# MM_Motor_Driver.net
KiCad netlist of a schematic drawn in Altium Designer
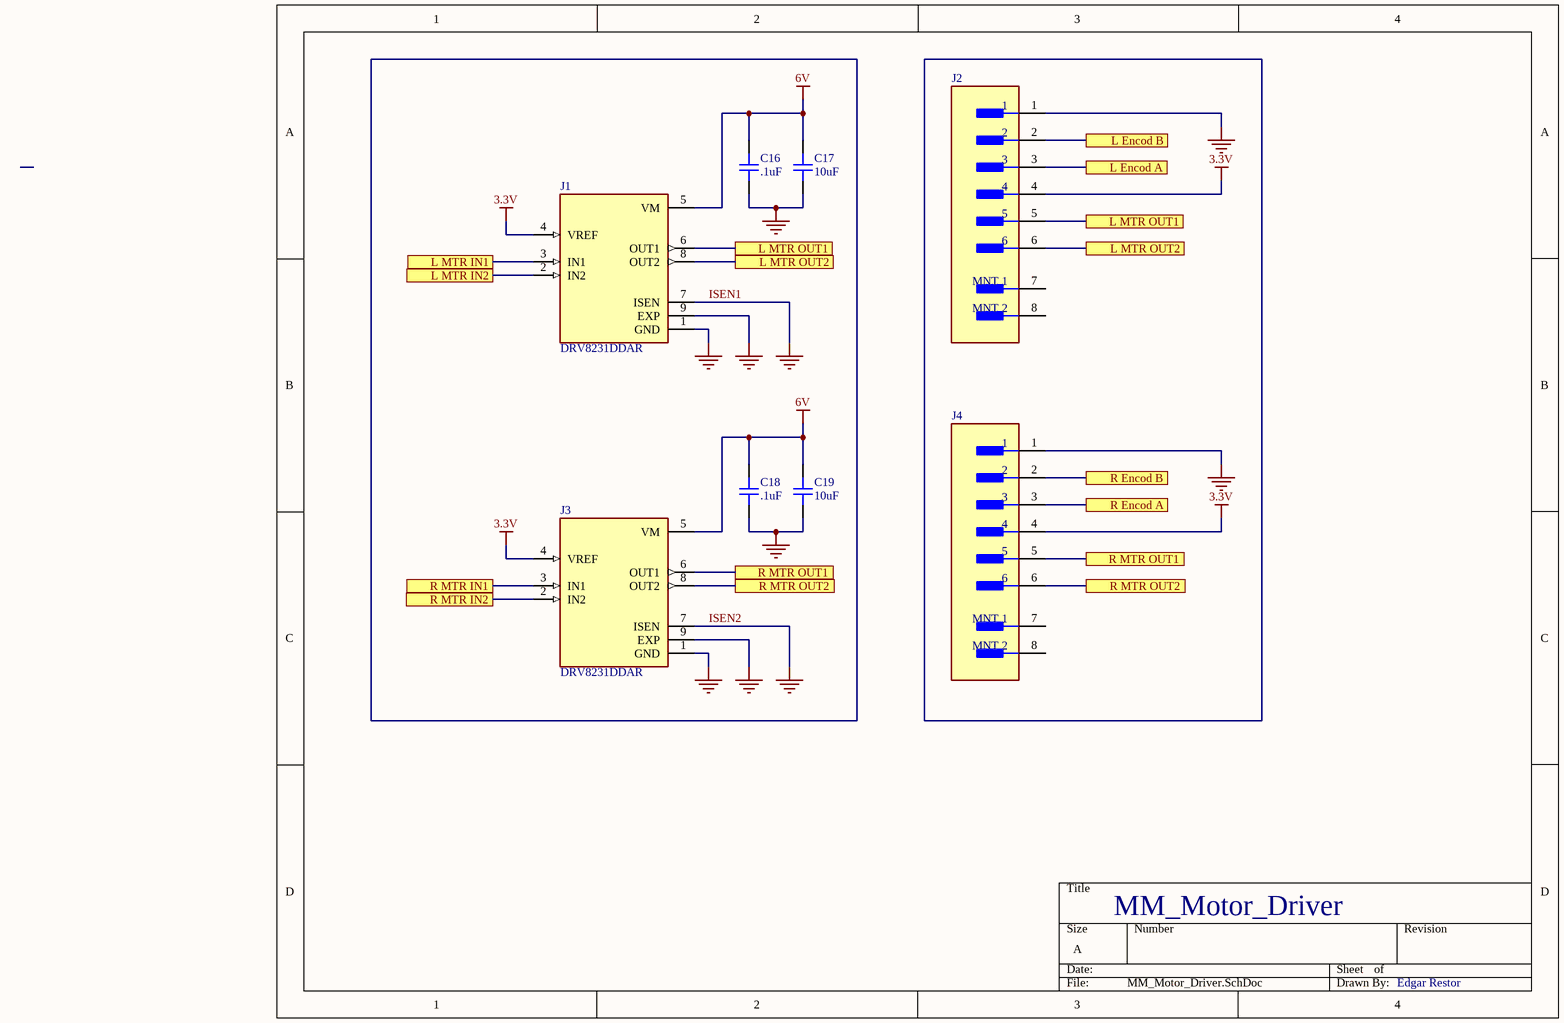
[diagram p0: MM_Motor_Driver.SchDoc]

(export (version "E")
  (design (tool "Eeschema 10.0.6"))
  (components
    (comp (ref "C16")
      (value ".1uF")
      (footprint "CAP_0603")
      (description "Capacitor SMD 0603")
      (libsource (lib "Schematic-Lib-PhilsLab") (part "CAP_0603"))
    )
    (comp (ref "C17")
      (value "10uF")
      (footprint "CAP_0603")
      (description "Capacitor SMD 0603")
      (libsource (lib "Schematic-Lib-PhilsLab") (part "CAP_0603"))
    )
    (comp (ref "C18")
      (value ".1uF")
      (footprint "CAP_0603")
      (description "Capacitor SMD 0603")
      (libsource (lib "Schematic-Lib-PhilsLab") (part "CAP_0603"))
    )
    (comp (ref "C19")
      (value "10uF")
      (footprint "CAP_0603")
      (description "Capacitor SMD 0603")
      (libsource (lib "Schematic-Lib-PhilsLab") (part "CAP_0603"))
    )
    (comp (ref "J1")
      (value "DRV8231DDAR")
      (footprint "IC_DRV8231DDAR")
      (description "35-V, 3.7-A H-bridge motor driver with integrated current regulation")
      (libsource (lib "Schematic-Lib-PhilsLab") (part "DRV8231DDAR"))
    )
    (comp (ref "J2")
      (value "BM06B-SRSS-TBT(LF)(SN)")
      (footprint "FP-BM06B-SRSS-TBT_LF_SN-MFG")
      (description "CONN HEADER SMD 6POS 1MM")
      (libsource (lib "Altium Content Vault") (part "ed24c53d9ba001d1a2a686240a95171"))
    )
    (comp (ref "J3")
      (value "DRV8231DDAR")
      (footprint "IC_DRV8231DDAR")
      (description "35-V, 3.7-A H-bridge motor driver with integrated current regulation")
      (libsource (lib "Schematic-Lib-PhilsLab") (part "DRV8231DDAR"))
    )
    (comp (ref "J4")
      (value "BM06B-SRSS-TBT(LF)(SN)")
      (footprint "FP-BM06B-SRSS-TBT_LF_SN-MFG")
      (description "CONN HEADER SMD 6POS 1MM")
      (libsource (lib "Altium Content Vault") (part "ed24c53d9ba001d1a2a686240a95171"))
    )
  )
  (nets
    (net (code "1") (name "/L Encod A") (class "Default")
      (node (ref "J2") (pin "3") (pinfunction "3_3") (pintype "passive"))
    )
    (net (code "2") (name "/L Encod B") (class "Default")
      (node (ref "J2") (pin "2") (pinfunction "2_2") (pintype "passive"))
    )
    (net (code "3") (name "/L MTR IN1") (class "Default")
      (node (ref "J1") (pin "3") (pinfunction "IN1_3") (pintype "input"))
    )
    (net (code "4") (name "/L MTR IN2") (class "Default")
      (node (ref "J1") (pin "2") (pinfunction "IN2_2") (pintype "input"))
    )
    (net (code "5") (name "/L MTR OUT1") (class "Default")
      (node (ref "J1") (pin "6") (pinfunction "OUT1_6") (pintype "output"))
      (node (ref "J2") (pin "5") (pinfunction "5_5") (pintype "passive"))
    )
    (net (code "6") (name "/L MTR OUT2") (class "Default")
      (node (ref "J1") (pin "8") (pinfunction "OUT2_8") (pintype "output"))
      (node (ref "J2") (pin "6") (pinfunction "6_6") (pintype "passive"))
    )
    (net (code "7") (name "/R Encod A") (class "Default")
      (node (ref "J4") (pin "3") (pinfunction "3_3") (pintype "passive"))
    )
    (net (code "8") (name "/R Encod B") (class "Default")
      (node (ref "J4") (pin "2") (pinfunction "2_2") (pintype "passive"))
    )
    (net (code "9") (name "/R MTR IN1") (class "Default")
      (node (ref "J3") (pin "3") (pinfunction "IN1_3") (pintype "input"))
    )
    (net (code "10") (name "/R MTR IN2") (class "Default")
      (node (ref "J3") (pin "2") (pinfunction "IN2_2") (pintype "input"))
    )
    (net (code "11") (name "/R MTR OUT1") (class "Default")
      (node (ref "J3") (pin "6") (pinfunction "OUT1_6") (pintype "output"))
      (node (ref "J4") (pin "5") (pinfunction "5_5") (pintype "passive"))
    )
    (net (code "12") (name "/R MTR OUT2") (class "Default")
      (node (ref "J3") (pin "8") (pinfunction "OUT2_8") (pintype "output"))
      (node (ref "J4") (pin "6") (pinfunction "6_6") (pintype "passive"))
    )
    (net (code "13") (name "3.3V") (class "Default")
      (node (ref "J1") (pin "4") (pinfunction "VREF_4") (pintype "input"))
      (node (ref "J2") (pin "4") (pinfunction "4_4") (pintype "passive"))
      (node (ref "J3") (pin "4") (pinfunction "VREF_4") (pintype "input"))
      (node (ref "J4") (pin "4") (pinfunction "4_4") (pintype "passive"))
    )
    (net (code "14") (name "6V") (class "Default")
      (node (ref "C16") (pin "2") (pinfunction "2_2") (pintype "passive"))
      (node (ref "C17") (pin "2") (pinfunction "2_2") (pintype "passive"))
      (node (ref "C18") (pin "2") (pinfunction "2_2") (pintype "passive"))
      (node (ref "C19") (pin "2") (pinfunction "2_2") (pintype "passive"))
      (node (ref "J1") (pin "5") (pinfunction "VM_5") (pintype "power_in"))
      (node (ref "J3") (pin "5") (pinfunction "VM_5") (pintype "power_in"))
    )
    (net (code "15") (name "GND") (class "Default")
      (node (ref "C16") (pin "1") (pinfunction "1_1") (pintype "passive"))
      (node (ref "C17") (pin "1") (pinfunction "1_1") (pintype "passive"))
      (node (ref "C18") (pin "1") (pinfunction "1_1") (pintype "passive"))
      (node (ref "C19") (pin "1") (pinfunction "1_1") (pintype "passive"))
      (node (ref "J1") (pin "1") (pinfunction "GND_1") (pintype "power_in"))
      (node (ref "J1") (pin "7") (pinfunction "ISEN_7") (pintype "power_in"))
      (node (ref "J1") (pin "9") (pinfunction "EXP_9") (pintype "power_in"))
      (node (ref "J2") (pin "1") (pinfunction "1_1") (pintype "passive"))
      (node (ref "J3") (pin "1") (pinfunction "GND_1") (pintype "power_in"))
      (node (ref "J3") (pin "7") (pinfunction "ISEN_7") (pintype "power_in"))
      (node (ref "J3") (pin "9") (pinfunction "EXP_9") (pintype "power_in"))
      (node (ref "J4") (pin "1") (pinfunction "1_1") (pintype "passive"))
    )
    (net (code "16") (name "unconnected-(J2-MNT_1-Pad7)") (class "Default")
      (node (ref "J2") (pin "7") (pinfunction "MNT_1_7") (pintype "passive"))
    )
    (net (code "17") (name "unconnected-(J2-MNT_2-Pad8)") (class "Default")
      (node (ref "J2") (pin "8") (pinfunction "MNT_2_8") (pintype "passive"))
    )
    (net (code "18") (name "unconnected-(J4-MNT_1-Pad7)") (class "Default")
      (node (ref "J4") (pin "7") (pinfunction "MNT_1_7") (pintype "passive"))
    )
    (net (code "19") (name "unconnected-(J4-MNT_2-Pad8)") (class "Default")
      (node (ref "J4") (pin "8") (pinfunction "MNT_2_8") (pintype "passive"))
    )
  )
)
